# basic_arduino_Schematic_1.net
KiCad netlist of a schematic drawn in EAGLE
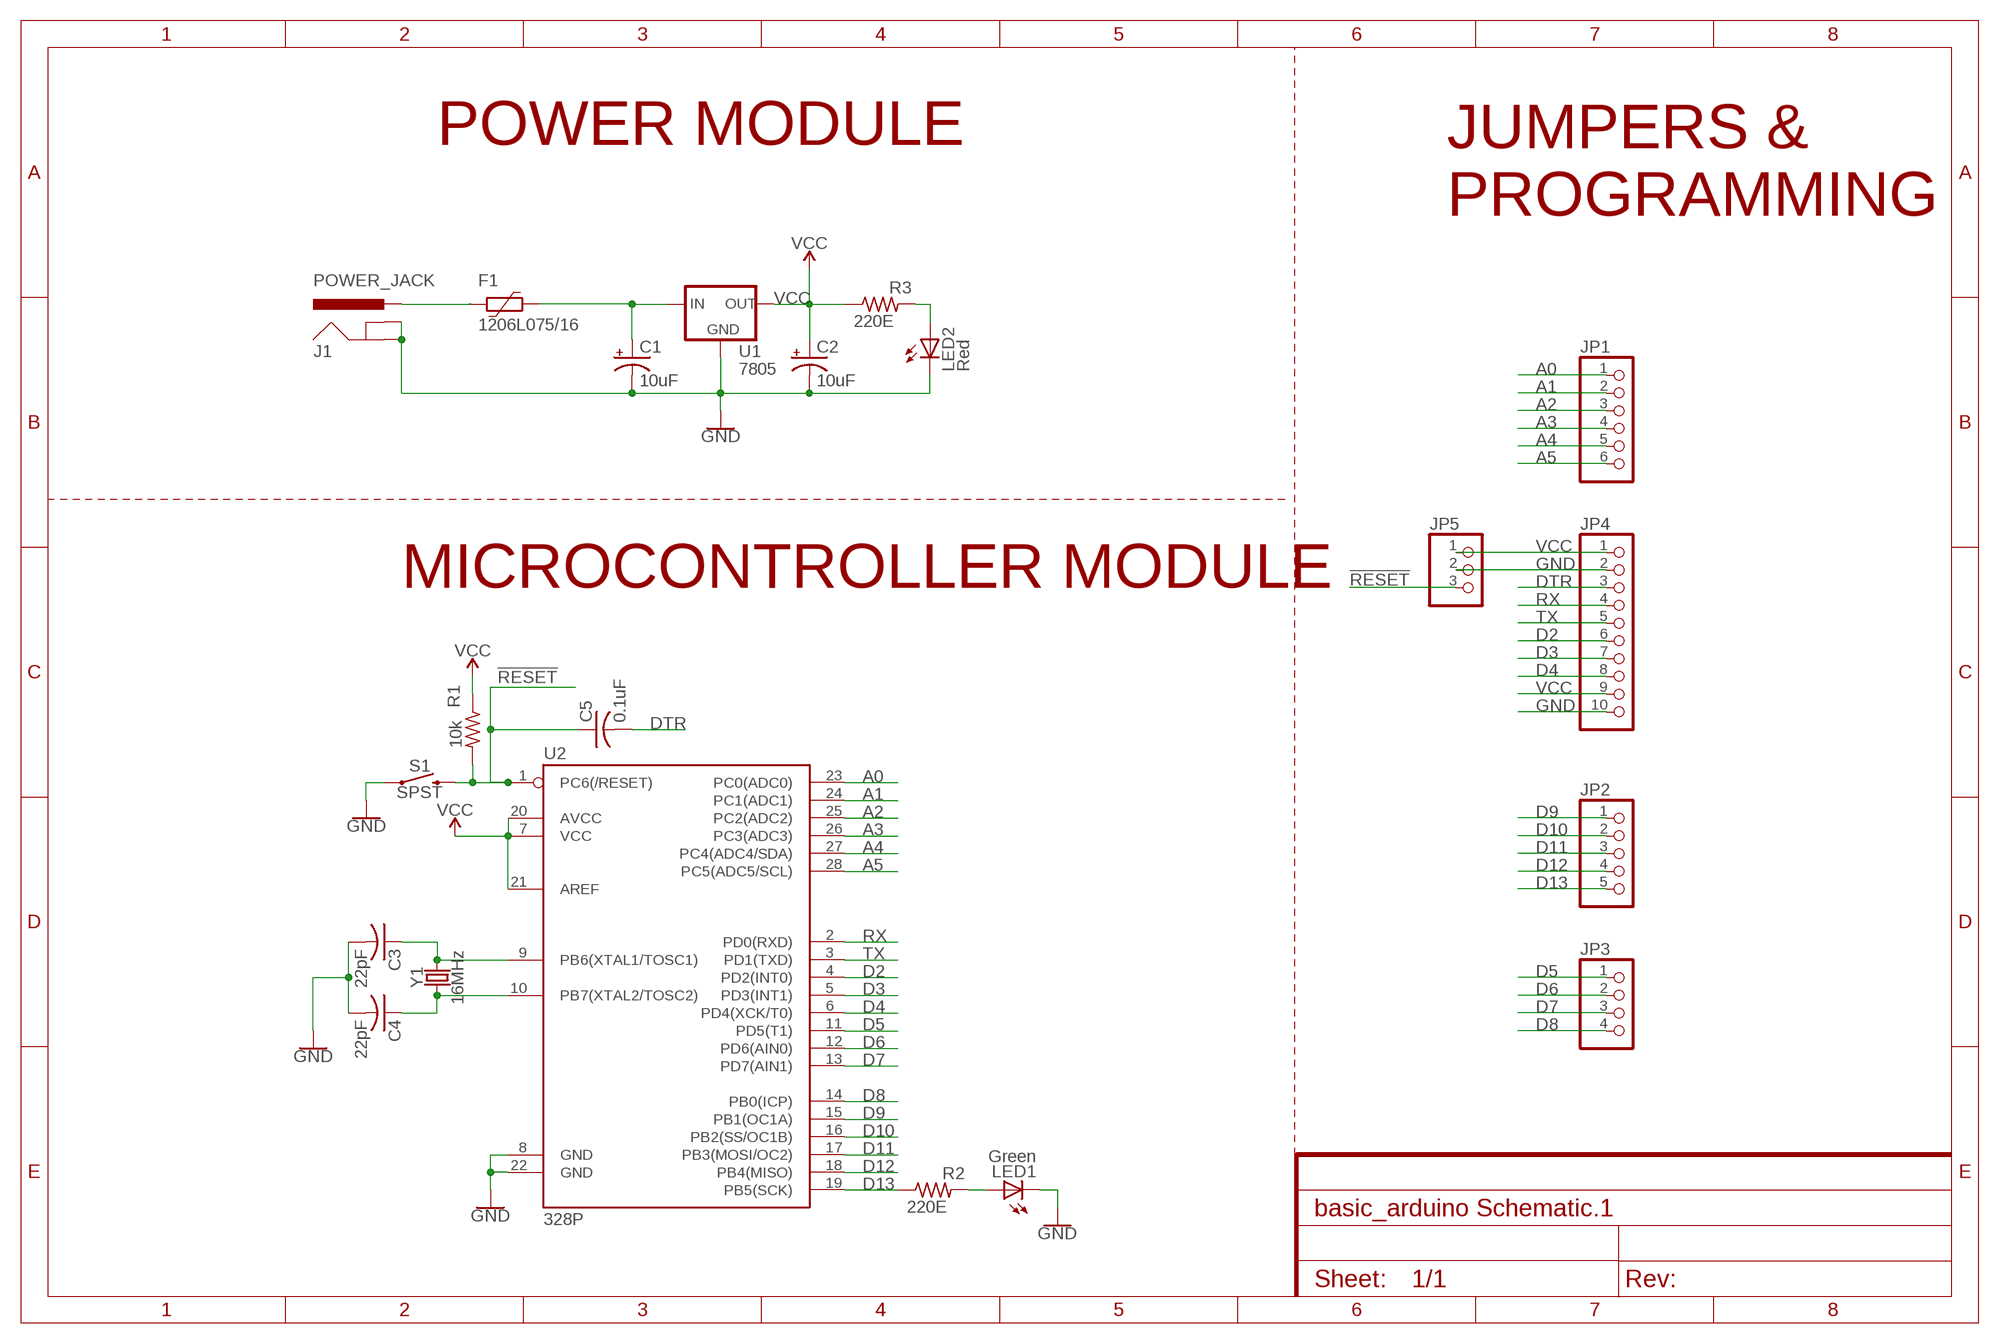
[diagram p0: schematic, sheet 1]

(export (version "E")
  (design (tool "Eeschema 10.0.6"))
  (components
    (comp (ref "C1")
      (value "10uF")
      (footprint "eagle-import:E2,5-6")
      (libsource (lib "eagle-import") (part "CPOL-USE2.5-6"))
    )
    (comp (ref "C2")
      (value "10uF")
      (footprint "eagle-import:E2,5-6")
      (libsource (lib "eagle-import") (part "CPOL-USE2.5-6"))
    )
    (comp (ref "C3")
      (value "22pF")
      (footprint "eagle-import:C025-025X050")
      (libsource (lib "eagle-import") (part "C-US025-025X050"))
    )
    (comp (ref "C4")
      (value "22pF")
      (footprint "eagle-import:C025-025X050")
      (libsource (lib "eagle-import") (part "C-US025-025X050"))
    )
    (comp (ref "C5")
      (value "0.1uF")
      (footprint "eagle-import:C025-025X050")
      (libsource (lib "eagle-import") (part "C-US025-025X050"))
    )
    (comp (ref "F1")
      (value "1206L075/16")
      (footprint "eagle-import:1206L")
      (fields (field (name "MF") "Littelfuse"))
      (libsource (lib "eagle-import") (part "?1206L075/16"))
    )
    (comp (ref "J1")
      (value "POWER_JACK")
      (footprint "eagle-import:POWER_JACK_PTH")
      (libsource (lib "eagle-import") (part "POWER_JACK"))
    )
    (comp (ref "JP1")
      (value "PINHD-1X6")
      (footprint "eagle-import:1X06")
      (libsource (lib "eagle-import") (part "PINHD-1X6"))
    )
    (comp (ref "JP2")
      (value "PINHD-1X5")
      (footprint "eagle-import:1X05")
      (libsource (lib "eagle-import") (part "PINHD-1X5"))
    )
    (comp (ref "JP3")
      (value "PINHD-1X4")
      (footprint "eagle-import:1X04")
      (libsource (lib "eagle-import") (part "PINHD-1X4"))
    )
    (comp (ref "JP4")
      (value "PINHD-1X10")
      (footprint "eagle-import:1X10")
      (libsource (lib "eagle-import") (part "PINHD-1X10"))
    )
    (comp (ref "JP5")
      (value "PINHD-1X3")
      (footprint "eagle-import:1X03")
      (libsource (lib "eagle-import") (part "PINHD-1X3"))
    )
    (comp (ref "LED1")
      (value "Green")
      (footprint "eagle-import:LED3MM")
      (libsource (lib "eagle-import") (part "LED3MM"))
    )
    (comp (ref "LED2")
      (value "Red")
      (footprint "eagle-import:LED3MM")
      (libsource (lib "eagle-import") (part "LED3MM"))
    )
    (comp (ref "R1")
      (value "10k")
      (footprint "eagle-import:0204_7")
      (libsource (lib "eagle-import") (part "R-US_0204/7"))
    )
    (comp (ref "R2")
      (value "220E")
      (footprint "eagle-import:0204_7")
      (libsource (lib "eagle-import") (part "R-US_0204/7"))
    )
    (comp (ref "R3")
      (value "220E")
      (footprint "eagle-import:0204_7")
      (libsource (lib "eagle-import") (part "R-US_0204/7"))
    )
    (comp (ref "S1")
      (value "SPST")
      (footprint "eagle-import:TACTILE_SWITCH_PTH_6.0MM")
      (libsource (lib "eagle-import") (part "MOMENTARY-SWITCH-SPST-PTH-6.0MM"))
    )
    (comp (ref "U1")
      (value "7805")
      (footprint "eagle-import:78XXS")
      (libsource (lib "eagle-import") (part "78XXS"))
    )
    (comp (ref "U2")
      (value "328P")
      (footprint "eagle-import:DIP28")
      (libsource (lib "eagle-import") (part "ATMEGA328P_PDIP"))
    )
    (comp (ref "Y1")
      (value "16MHz")
      (footprint "eagle-import:HC49US")
      (libsource (lib "eagle-import") (part "CRYSTAL-16MHZPTH-HC49US"))
    )
  )
  (nets
    (net (code "1") (name "/A0") (class "Default")
      (node (ref "JP1") (pin "1") (pinfunction "1_1") (pintype "passive"))
      (node (ref "U2") (pin "23") (pinfunction "PC0(ADC0)_23") (pintype "bidirectional"))
    )
    (net (code "2") (name "/A1") (class "Default")
      (node (ref "JP1") (pin "2") (pinfunction "2_2") (pintype "passive"))
      (node (ref "U2") (pin "24") (pinfunction "PC1(ADC1)_24") (pintype "bidirectional"))
    )
    (net (code "3") (name "/A2") (class "Default")
      (node (ref "JP1") (pin "3") (pinfunction "3_3") (pintype "passive"))
      (node (ref "U2") (pin "25") (pinfunction "PC2(ADC2)_25") (pintype "bidirectional"))
    )
    (net (code "4") (name "/A3") (class "Default")
      (node (ref "JP1") (pin "4") (pinfunction "4_4") (pintype "passive"))
      (node (ref "U2") (pin "26") (pinfunction "PC3(ADC3)_26") (pintype "bidirectional"))
    )
    (net (code "5") (name "/A4") (class "Default")
      (node (ref "JP1") (pin "5") (pinfunction "5_5") (pintype "passive"))
      (node (ref "U2") (pin "27") (pinfunction "PC4(ADC4/SDA)_27") (pintype "bidirectional"))
    )
    (net (code "6") (name "/A5") (class "Default")
      (node (ref "JP1") (pin "6") (pinfunction "6_6") (pintype "passive"))
      (node (ref "U2") (pin "28") (pinfunction "PC5(ADC5/SCL)_28") (pintype "bidirectional"))
    )
    (net (code "7") (name "/D2") (class "Default")
      (node (ref "JP4") (pin "6") (pinfunction "6_6") (pintype "passive"))
      (node (ref "U2") (pin "4") (pinfunction "PD2(INT0)_4") (pintype "bidirectional"))
    )
    (net (code "8") (name "/D3") (class "Default")
      (node (ref "JP4") (pin "7") (pinfunction "7_7") (pintype "passive"))
      (node (ref "U2") (pin "5") (pinfunction "PD3(INT1)_5") (pintype "bidirectional"))
    )
    (net (code "9") (name "/D4") (class "Default")
      (node (ref "JP4") (pin "8") (pinfunction "8_8") (pintype "passive"))
      (node (ref "U2") (pin "6") (pinfunction "PD4(XCK/T0)_6") (pintype "bidirectional"))
    )
    (net (code "10") (name "/D5") (class "Default")
      (node (ref "JP3") (pin "1") (pinfunction "1_1") (pintype "passive"))
      (node (ref "U2") (pin "11") (pinfunction "PD5(T1)_11") (pintype "bidirectional"))
    )
    (net (code "11") (name "/D6") (class "Default")
      (node (ref "JP3") (pin "2") (pinfunction "2_2") (pintype "passive"))
      (node (ref "U2") (pin "12") (pinfunction "PD6(AIN0)_12") (pintype "bidirectional"))
    )
    (net (code "12") (name "/D7") (class "Default")
      (node (ref "JP3") (pin "3") (pinfunction "3_3") (pintype "passive"))
      (node (ref "U2") (pin "13") (pinfunction "PD7(AIN1)_13") (pintype "bidirectional"))
    )
    (net (code "13") (name "/D8") (class "Default")
      (node (ref "JP3") (pin "4") (pinfunction "4_4") (pintype "passive"))
      (node (ref "U2") (pin "14") (pinfunction "PB0(ICP)_14") (pintype "bidirectional"))
    )
    (net (code "14") (name "/D9") (class "Default")
      (node (ref "JP2") (pin "1") (pinfunction "1_1") (pintype "passive"))
      (node (ref "U2") (pin "15") (pinfunction "PB1(OC1A)_15") (pintype "bidirectional"))
    )
    (net (code "15") (name "/D10") (class "Default")
      (node (ref "JP2") (pin "2") (pinfunction "2_2") (pintype "passive"))
      (node (ref "U2") (pin "16") (pinfunction "PB2(SS/OC1B)_16") (pintype "bidirectional"))
    )
    (net (code "16") (name "/D11") (class "Default")
      (node (ref "JP2") (pin "3") (pinfunction "3_3") (pintype "passive"))
      (node (ref "U2") (pin "17") (pinfunction "PB3(MOSI/OC2)_17") (pintype "bidirectional"))
    )
    (net (code "17") (name "/D12") (class "Default")
      (node (ref "JP2") (pin "4") (pinfunction "4_4") (pintype "passive"))
      (node (ref "U2") (pin "18") (pinfunction "PB4(MISO)_18") (pintype "bidirectional"))
    )
    (net (code "18") (name "/D13") (class "Default")
      (node (ref "JP2") (pin "5") (pinfunction "5_5") (pintype "passive"))
      (node (ref "R2") (pin "1") (pinfunction "1_1") (pintype "passive"))
      (node (ref "U2") (pin "19") (pinfunction "PB5(SCK)_19") (pintype "bidirectional"))
    )
    (net (code "19") (name "/DTR") (class "Default")
      (node (ref "C5") (pin "2") (pinfunction "2_2") (pintype "passive"))
      (node (ref "JP4") (pin "3") (pinfunction "3_3") (pintype "passive"))
    )
    (net (code "20") (name "/RX") (class "Default")
      (node (ref "JP4") (pin "4") (pinfunction "4_4") (pintype "passive"))
      (node (ref "U2") (pin "2") (pinfunction "PD0(RXD)_2") (pintype "bidirectional"))
    )
    (net (code "21") (name "/TX") (class "Default")
      (node (ref "JP4") (pin "5") (pinfunction "5_5") (pintype "passive"))
      (node (ref "U2") (pin "3") (pinfunction "PD1(TXD)_3") (pintype "bidirectional"))
    )
    (net (code "22") (name "/~{RESET}") (class "Default")
      (node (ref "C5") (pin "1") (pinfunction "1_1") (pintype "passive"))
      (node (ref "JP5") (pin "3") (pinfunction "3_3") (pintype "passive"))
      (node (ref "R1") (pin "2") (pinfunction "2_2") (pintype "passive"))
      (node (ref "S1") (pin "3") (pinfunction "2_3") (pintype "passive"))
      (node (ref "U2") (pin "1") (pinfunction "PC6(/RESET)_1") (pintype "bidirectional"))
    )
    (net (code "23") (name "GND") (class "Default")
      (node (ref "C1") (pin "-") (pinfunction "-_-") (pintype "passive"))
      (node (ref "C2") (pin "-") (pinfunction "-_-") (pintype "passive"))
      (node (ref "C3") (pin "2") (pinfunction "2_2") (pintype "passive"))
      (node (ref "C4") (pin "2") (pinfunction "2_2") (pintype "passive"))
      (node (ref "J1") (pin "GND") (pinfunction "GND_GND") (pintype "bidirectional"))
      (node (ref "J1") (pin "GNDBREAK") (pinfunction "GNDBREAK_GNDBREAK") (pintype "bidirectional"))
      (node (ref "JP4") (pin "10") (pinfunction "10_10") (pintype "passive"))
      (node (ref "JP4") (pin "2") (pinfunction "2_2") (pintype "passive"))
      (node (ref "JP5") (pin "2") (pinfunction "2_2") (pintype "passive"))
      (node (ref "LED1") (pin "K") (pinfunction "C_K") (pintype "passive"))
      (node (ref "LED2") (pin "K") (pinfunction "C_K") (pintype "passive"))
      (node (ref "S1") (pin "1") (pinfunction "1_1") (pintype "passive"))
      (node (ref "U1") (pin "GND") (pinfunction "GND_GND") (pintype "input"))
      (node (ref "U2") (pin "22") (pinfunction "GND_22") (pintype "bidirectional"))
      (node (ref "U2") (pin "8") (pinfunction "GND_8") (pintype "bidirectional"))
    )
    (net (code "24") (name "Net-(C1-Pad+)") (class "Default")
      (node (ref "C1") (pin "+") (pinfunction "+_+") (pintype "passive"))
      (node (ref "F1") (pin "1") (pinfunction "1_1") (pintype "passive"))
      (node (ref "U1") (pin "IN") (pinfunction "IN_IN") (pintype "input"))
    )
    (net (code "25") (name "Net-(F1-Pad2)") (class "Default")
      (node (ref "F1") (pin "2") (pinfunction "2_2") (pintype "passive"))
      (node (ref "J1") (pin "PWR") (pinfunction "PWR_PWR") (pintype "bidirectional"))
    )
    (net (code "26") (name "Net-(LED1-PadA)") (class "Default")
      (node (ref "LED1") (pin "A") (pinfunction "A_A") (pintype "passive"))
      (node (ref "R2") (pin "2") (pinfunction "2_2") (pintype "passive"))
    )
    (net (code "27") (name "Net-(LED2-PadA)") (class "Default")
      (node (ref "LED2") (pin "A") (pinfunction "A_A") (pintype "passive"))
      (node (ref "R3") (pin "2") (pinfunction "2_2") (pintype "passive"))
    )
    (net (code "28") (name "Net-(U2-PB6(XTAL1{slash}TOSC1))") (class "Default")
      (node (ref "C3") (pin "1") (pinfunction "1_1") (pintype "passive"))
      (node (ref "U2") (pin "9") (pinfunction "PB6(XTAL1/TOSC1)_9") (pintype "bidirectional"))
      (node (ref "Y1") (pin "2") (pinfunction "2_2") (pintype "passive"))
    )
    (net (code "29") (name "Net-(U2-PB7(XTAL2{slash}TOSC2))") (class "Default")
      (node (ref "C4") (pin "1") (pinfunction "1_1") (pintype "passive"))
      (node (ref "U2") (pin "10") (pinfunction "PB7(XTAL2/TOSC2)_10") (pintype "bidirectional"))
      (node (ref "Y1") (pin "1") (pinfunction "1_1") (pintype "passive"))
    )
    (net (code "30") (name "VCC") (class "Default")
      (node (ref "C2") (pin "+") (pinfunction "+_+") (pintype "passive"))
      (node (ref "JP4") (pin "1") (pinfunction "1_1") (pintype "passive"))
      (node (ref "JP4") (pin "9") (pinfunction "9_9") (pintype "passive"))
      (node (ref "JP5") (pin "1") (pinfunction "1_1") (pintype "passive"))
      (node (ref "R1") (pin "1") (pinfunction "1_1") (pintype "passive"))
      (node (ref "R3") (pin "1") (pinfunction "1_1") (pintype "passive"))
      (node (ref "U1") (pin "OUT") (pinfunction "OUT_OUT") (pintype "passive"))
      (node (ref "U2") (pin "20") (pinfunction "AVCC_20") (pintype "bidirectional"))
      (node (ref "U2") (pin "21") (pinfunction "AREF_21") (pintype "bidirectional"))
      (node (ref "U2") (pin "7") (pinfunction "VCC_7") (pintype "bidirectional"))
    )
  )
)
